# Boost_DC_DC.net
KiCad netlist of a schematic drawn in Altium Designer
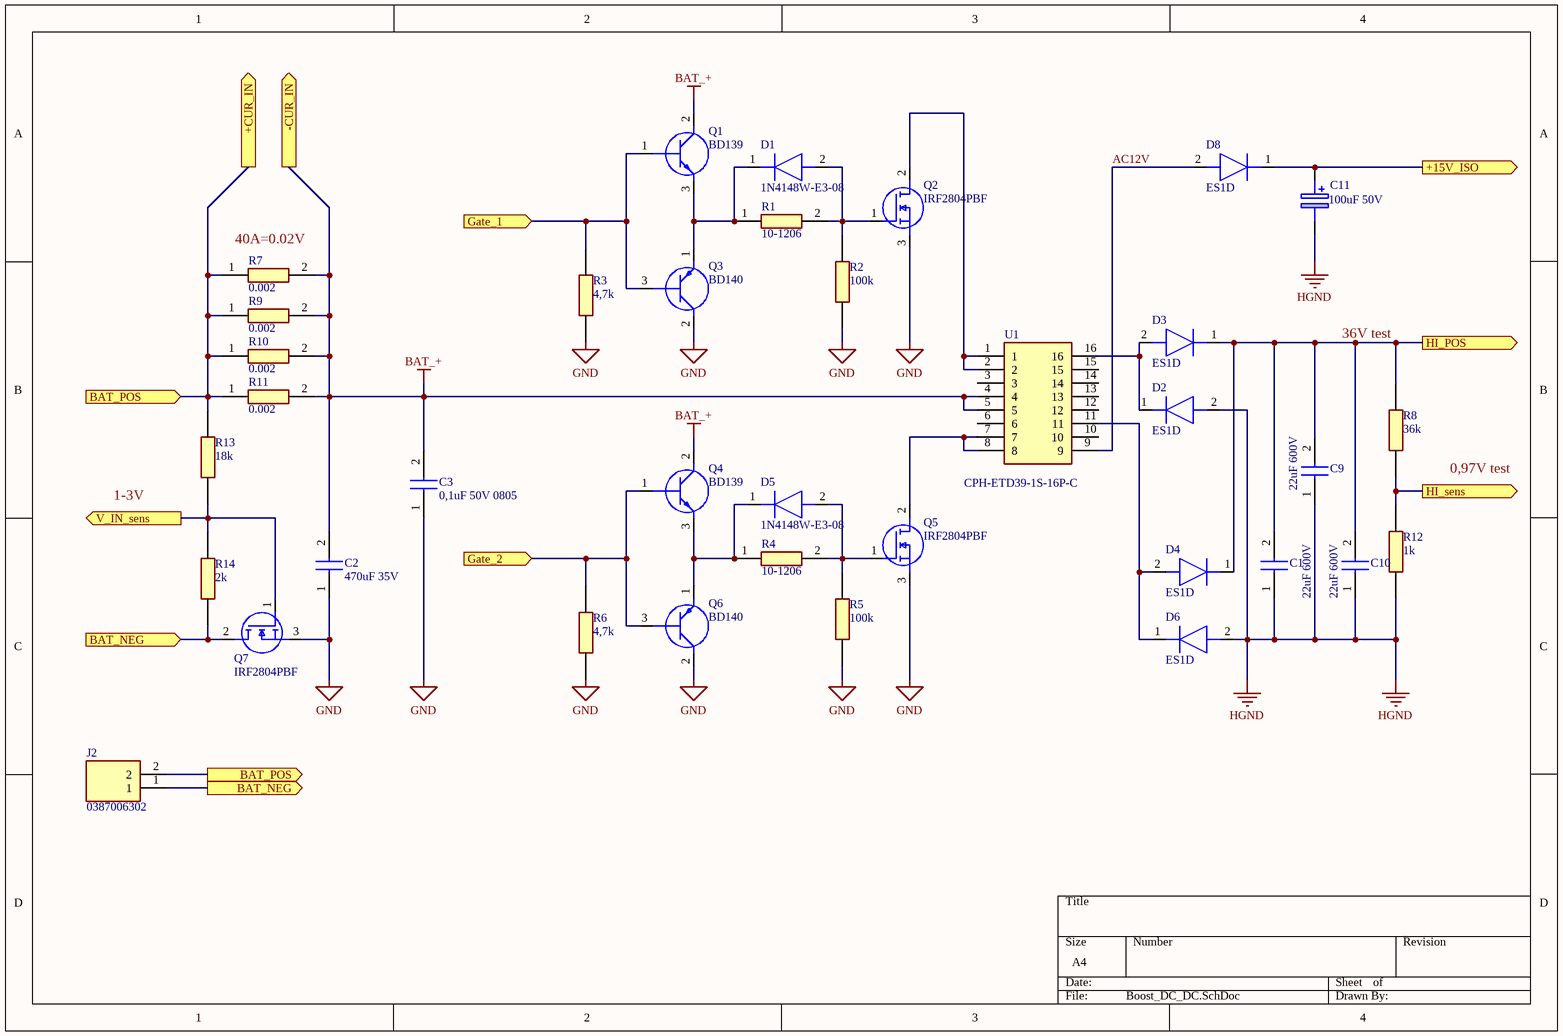
[diagram p0: Boost_DC_DC.SchDoc]

(export (version "E")
  (design (tool "Eeschema 10.0.6"))
  (components
    (comp (ref "C1")
      (value "22uF 600V")
      (footprint "SamacSys:CAPPRD750W80D1625H2700")
      (description "Capacitor")
      (libsource (lib "*") (part "UPW1H102MHD"))
    )
    (comp (ref "C2")
      (value "470uF 35V")
      (footprint "SamacSys:CAPPRD750W80D1625H2700")
      (description "Capacitor")
      (libsource (lib "*") (part "UPW1H102MHD"))
    )
    (comp (ref "C3")
      (value "0,1uF 50V 0805")
      (footprint "SamacSys:CAPC2012X90N")
      (description "Capacitor")
      (libsource (lib "*") (part "MCMT21N470F250CT"))
    )
    (comp (ref "C9")
      (value "22uF 600V")
      (footprint "SamacSys:CAPPRD750W80D1625H2700")
      (description "Capacitor")
      (libsource (lib "*") (part "UPW1H102MHD"))
    )
    (comp (ref "C10")
      (value "22uF 600V")
      (footprint "SamacSys:CAPPRD750W80D1625H2700")
      (description "Capacitor")
      (libsource (lib "*") (part "UPW1H102MHD"))
    )
    (comp (ref "C11")
      (value "100uF 50V")
      (footprint "CAPPRD500W60D870H1200")
      (description "Aluminum Electrolytic Capacitors - Radial Leaded 100uF 50V 20% Radial")
      (fields
        (field (name "MANUFACTURER_PART_NUMBER") "MAL203690109E3")
        (field (name "MOUSER PART NUMBER") "594-2222-036-90109")
      )
      (libsource (lib "MAL203690109E3") (part "MAL203690109E3"))
    )
    (comp (ref "D1")
      (value "1N4148W-E3-08")
      (footprint "SamacSys:SOD3716X135N")
      (description "Diode")
      (fields (field (name "MOUSER PART NUMBER") "78-1N4148W-E3-08"))
      (libsource (lib "*") (part "1N4148W-E3-08"))
    )
    (comp (ref "D2")
      (value "ES1D")
      (footprint "SamacSys:DIOM5226X295N")
      (description "Diode")
      (libsource (lib "SamacSys") (part "ES1D"))
    )
    (comp (ref "D3")
      (value "ES1D")
      (footprint "SamacSys:DIOM5226X295N")
      (description "Diode")
      (libsource (lib "SamacSys") (part "ES1D"))
    )
    (comp (ref "D4")
      (value "ES1D")
      (footprint "SamacSys:DIOM5226X295N")
      (description "Diode")
      (libsource (lib "SamacSys") (part "ES1D"))
    )
    (comp (ref "D5")
      (value "1N4148W-E3-08")
      (footprint "SamacSys:SOD3716X135N")
      (description "Diode")
      (fields (field (name "MOUSER PART NUMBER") "78-1N4148W-E3-08"))
      (libsource (lib "*") (part "1N4148W-E3-08"))
    )
    (comp (ref "D6")
      (value "ES1D")
      (footprint "SamacSys:DIOM5226X295N")
      (description "Diode")
      (libsource (lib "SamacSys") (part "ES1D"))
    )
    (comp (ref "D8")
      (value "ES1D")
      (footprint "SamacSys:DIOM5226X295N")
      (description "Diode")
      (libsource (lib "SamacSys") (part "ES1D"))
    )
    (comp (ref "J2")
      (value "0387006302")
      (footprint "SamacSys:0387006302")
      (description "Connector")
      (libsource (lib "*") (part "0387006302"))
    )
    (comp (ref "Q1")
      (value "BD139")
      (footprint "SamacSys:TO254P290X760X1320-3P")
      (description "Transistor BJT NPN")
      (fields (field (name "MOUSER PART NUMBER") "511-BD139"))
      (libsource (lib "*") (part "BD139"))
    )
    (comp (ref "Q2")
      (value "IRF2804PBF")
      (footprint "SamacSys:TO254P482X1016X2192-3P")
      (description "MOSFET (N-Channel)")
      (fields (field (name "MOUSER PART NUMBER") "942-IRF2804PBF"))
      (libsource (lib "*") (part "IRF2804PBF"))
    )
    (comp (ref "Q3")
      (value "BD140")
      (footprint "SamacSys:TO229P300X760X1364-3P")
      (description "Transistor BJT PNP")
      (fields
        (field (name "MANUFACTURER_PART_NUMBER") "BD138")
        (field (name "MOUSER PART NUMBER") "863-BD138")
      )
      (libsource (lib "*") (part "BD138"))
    )
    (comp (ref "Q4")
      (value "BD139")
      (footprint "SamacSys:TO254P290X760X1320-3P")
      (description "Transistor BJT NPN")
      (fields (field (name "MOUSER PART NUMBER") "511-BD139"))
      (libsource (lib "*") (part "BD139"))
    )
    (comp (ref "Q5")
      (value "IRF2804PBF")
      (footprint "SamacSys:TO254P482X1016X2192-3P")
      (description "MOSFET (N-Channel)")
      (fields (field (name "MOUSER PART NUMBER") "942-IRF2804PBF"))
      (libsource (lib "*") (part "IRF2804PBF"))
    )
    (comp (ref "Q6")
      (value "BD140")
      (footprint "SamacSys:TO229P300X760X1364-3P")
      (description "Transistor BJT PNP")
      (fields
        (field (name "MANUFACTURER_PART_NUMBER") "BD138")
        (field (name "MOUSER PART NUMBER") "863-BD138")
      )
      (libsource (lib "*") (part "BD138"))
    )
    (comp (ref "Q7")
      (value "IRF2804PBF")
      (footprint "SamacSys:TO254P482X1016X2192-3P")
      (description "MOSFET (N-Channel)")
      (fields (field (name "MOUSER PART NUMBER") "942-IRF2804PBF"))
      (libsource (lib "*") (part "IRF2804PBF"))
    )
    (comp (ref "R1")
      (value "10-1206")
      (footprint "SamacSys:RESC3116X75N")
      (description "Resistor")
      (libsource (lib "*") (part "MCMR12X1003FTL"))
    )
    (comp (ref "R2")
      (value "100k")
      (footprint "RESC2013X65N")
      (description "Resistor")
      (libsource (lib "SamacSys") (part "ERJP06J822V"))
    )
    (comp (ref "R3")
      (value "4,7k")
      (footprint "RESC2013X65N")
      (description "Resistor")
      (libsource (lib "SamacSys") (part "ERJP06J822V"))
    )
    (comp (ref "R4")
      (value "10-1206")
      (footprint "SamacSys:RESC3116X75N")
      (description "Resistor")
      (libsource (lib "*") (part "MCMR12X1003FTL"))
    )
    (comp (ref "R5")
      (value "100k")
      (footprint "RESC2013X65N")
      (description "Resistor")
      (libsource (lib "SamacSys") (part "ERJP06J822V"))
    )
    (comp (ref "R6")
      (value "4,7k")
      (footprint "RESC2013X65N")
      (description "Resistor")
      (libsource (lib "SamacSys") (part "ERJP06J822V"))
    )
    (comp (ref "R7")
      (value "0.002")
      (footprint "SamacSys:RESC3116X75N")
      (description "Resistor")
      (libsource (lib "*") (part "MCMR12X1003FTL"))
    )
    (comp (ref "R8")
      (value "36k")
      (footprint "RESC2013X65N")
      (description "Resistor")
      (libsource (lib "SamacSys") (part "ERJP06J822V"))
    )
    (comp (ref "R9")
      (value "0.002")
      (footprint "SamacSys:RESC3116X75N")
      (description "Resistor")
      (libsource (lib "*") (part "MCMR12X1003FTL"))
    )
    (comp (ref "R10")
      (value "0.002")
      (footprint "SamacSys:RESC3116X75N")
      (description "Resistor")
      (libsource (lib "*") (part "MCMR12X1003FTL"))
    )
    (comp (ref "R11")
      (value "0.002")
      (footprint "SamacSys:RESC3116X75N")
      (description "Resistor")
      (libsource (lib "*") (part "MCMR12X1003FTL"))
    )
    (comp (ref "R12")
      (value "1k")
      (footprint "RESC2013X65N")
      (description "Resistor")
      (libsource (lib "SamacSys") (part "ERJP06J822V"))
    )
    (comp (ref "R13")
      (value "18k")
      (footprint "RESC2013X65N")
      (description "Resistor")
      (libsource (lib "SamacSys") (part "ERJP06J822V"))
    )
    (comp (ref "R14")
      (value "2k")
      (footprint "RESC2013X65N")
      (description "Resistor")
      (libsource (lib "SamacSys") (part "ERJP06J822V"))
    )
    (comp (ref "U1")
      (value "CPH-ETD39-1S-16P-C")
      (footprint "SamacSys:DIPS3048W80P508L4460H3610Q16N")
      (description "Undefined or Miscellaneous")
      (libsource (lib "SamacSys") (part "CPH-ETD39-1S-16P-C"))
    )
  )
  (nets
    (net (code "1") (name "/+15V_ISO") (class "Default")
      (node (ref "C11") (pin "1") (pinfunction "+_1") (pintype "passive"))
      (node (ref "D8") (pin "1") (pinfunction "K_1") (pintype "passive"))
    )
    (net (code "2") (name "/+CUR_IN") (class "Default")
      (node (ref "J2") (pin "2") (pinfunction "2_2") (pintype "passive"))
      (node (ref "R10") (pin "1") (pinfunction "1_1") (pintype "passive"))
      (node (ref "R11") (pin "1") (pinfunction "1_1") (pintype "passive"))
      (node (ref "R13") (pin "2") (pinfunction "2_2") (pintype "passive"))
      (node (ref "R7") (pin "1") (pinfunction "1_1") (pintype "passive"))
      (node (ref "R9") (pin "1") (pinfunction "1_1") (pintype "passive"))
    )
    (net (code "3") (name "/AC12V") (class "Default")
      (node (ref "D8") (pin "2") (pinfunction "A_2") (pintype "passive"))
      (node (ref "U1") (pin "9") (pinfunction "9_9") (pintype "passive"))
    )
    (net (code "4") (name "/BAT_NEG") (class "Default")
      (node (ref "J2") (pin "1") (pinfunction "1_1") (pintype "passive"))
      (node (ref "Q7") (pin "2") (pinfunction "D_2") (pintype "passive"))
      (node (ref "R14") (pin "1") (pinfunction "1_1") (pintype "passive"))
    )
    (net (code "5") (name "/Gate_1") (class "Default")
      (node (ref "Q1") (pin "1") (pinfunction "B_1") (pintype "passive"))
      (node (ref "Q3") (pin "3") (pinfunction "B_3") (pintype "passive"))
      (node (ref "R3") (pin "2") (pinfunction "2_2") (pintype "passive"))
    )
    (net (code "6") (name "/Gate_2") (class "Default")
      (node (ref "Q4") (pin "1") (pinfunction "B_1") (pintype "passive"))
      (node (ref "Q6") (pin "3") (pinfunction "B_3") (pintype "passive"))
      (node (ref "R6") (pin "2") (pinfunction "2_2") (pintype "passive"))
    )
    (net (code "7") (name "/HI_POS") (class "Default")
      (node (ref "C1") (pin "2") (pinfunction "-_2") (pintype "passive"))
      (node (ref "C10") (pin "2") (pinfunction "-_2") (pintype "passive"))
      (node (ref "C9") (pin "2") (pinfunction "-_2") (pintype "passive"))
      (node (ref "D3") (pin "1") (pinfunction "K_1") (pintype "passive"))
      (node (ref "D4") (pin "1") (pinfunction "K_1") (pintype "passive"))
      (node (ref "R8") (pin "2") (pinfunction "2_2") (pintype "passive"))
    )
    (net (code "8") (name "/HI_sens") (class "Default")
      (node (ref "R12") (pin "2") (pinfunction "2_2") (pintype "passive"))
      (node (ref "R8") (pin "1") (pinfunction "1_1") (pintype "passive"))
    )
    (net (code "9") (name "/V_IN_sens") (class "Default")
      (node (ref "Q7") (pin "1") (pinfunction "G_1") (pintype "passive"))
      (node (ref "R13") (pin "1") (pinfunction "1_1") (pintype "passive"))
      (node (ref "R14") (pin "2") (pinfunction "2_2") (pintype "passive"))
    )
    (net (code "10") (name "BAT_+") (class "Default")
      (node (ref "C2") (pin "2") (pinfunction "-_2") (pintype "passive"))
      (node (ref "C3") (pin "2") (pinfunction "2_2") (pintype "passive"))
      (node (ref "Q1") (pin "2") (pinfunction "C_2") (pintype "passive"))
      (node (ref "Q4") (pin "2") (pinfunction "C_2") (pintype "passive"))
      (node (ref "R10") (pin "2") (pinfunction "2_2") (pintype "passive"))
      (node (ref "R11") (pin "2") (pinfunction "2_2") (pintype "passive"))
      (node (ref "R7") (pin "2") (pinfunction "2_2") (pintype "passive"))
      (node (ref "R9") (pin "2") (pinfunction "2_2") (pintype "passive"))
      (node (ref "U1") (pin "4") (pinfunction "4_4") (pintype "passive"))
      (node (ref "U1") (pin "5") (pinfunction "5_5") (pintype "passive"))
    )
    (net (code "11") (name "GND") (class "Default")
      (node (ref "C2") (pin "1") (pinfunction "+_1") (pintype "passive"))
      (node (ref "C3") (pin "1") (pinfunction "1_1") (pintype "passive"))
      (node (ref "Q2") (pin "3") (pinfunction "S_3") (pintype "passive"))
      (node (ref "Q3") (pin "2") (pinfunction "C_2") (pintype "passive"))
      (node (ref "Q5") (pin "3") (pinfunction "S_3") (pintype "passive"))
      (node (ref "Q6") (pin "2") (pinfunction "C_2") (pintype "passive"))
      (node (ref "Q7") (pin "3") (pinfunction "S_3") (pintype "passive"))
      (node (ref "R2") (pin "1") (pinfunction "1_1") (pintype "passive"))
      (node (ref "R3") (pin "1") (pinfunction "1_1") (pintype "passive"))
      (node (ref "R5") (pin "1") (pinfunction "1_1") (pintype "passive"))
      (node (ref "R6") (pin "1") (pinfunction "1_1") (pintype "passive"))
    )
    (net (code "12") (name "HGND") (class "Default")
      (node (ref "C1") (pin "1") (pinfunction "+_1") (pintype "passive"))
      (node (ref "C10") (pin "1") (pinfunction "+_1") (pintype "passive"))
      (node (ref "C11") (pin "2") (pinfunction "-_2") (pintype "passive"))
      (node (ref "C9") (pin "1") (pinfunction "+_1") (pintype "passive"))
      (node (ref "D2") (pin "2") (pinfunction "A_2") (pintype "passive"))
      (node (ref "D6") (pin "2") (pinfunction "A_2") (pintype "passive"))
      (node (ref "R12") (pin "1") (pinfunction "1_1") (pintype "passive"))
    )
    (net (code "13") (name "Net-(D1-A)") (class "Default")
      (node (ref "D1") (pin "2") (pinfunction "A_2") (pintype "passive"))
      (node (ref "Q2") (pin "1") (pinfunction "G_1") (pintype "passive"))
      (node (ref "R1") (pin "2") (pinfunction "2_2") (pintype "passive"))
      (node (ref "R2") (pin "2") (pinfunction "2_2") (pintype "passive"))
    )
    (net (code "14") (name "Net-(D1-K)") (class "Default")
      (node (ref "D1") (pin "1") (pinfunction "K_1") (pintype "passive"))
      (node (ref "Q1") (pin "3") (pinfunction "E_3") (pintype "passive"))
      (node (ref "Q3") (pin "1") (pinfunction "E_1") (pintype "passive"))
      (node (ref "R1") (pin "1") (pinfunction "1_1") (pintype "passive"))
    )
    (net (code "15") (name "Net-(D2-K)") (class "Default")
      (node (ref "D2") (pin "1") (pinfunction "K_1") (pintype "passive"))
      (node (ref "D3") (pin "2") (pinfunction "A_2") (pintype "passive"))
      (node (ref "U1") (pin "16") (pinfunction "16_16") (pintype "passive"))
    )
    (net (code "16") (name "Net-(D4-A)") (class "Default")
      (node (ref "D4") (pin "2") (pinfunction "A_2") (pintype "passive"))
      (node (ref "D6") (pin "1") (pinfunction "K_1") (pintype "passive"))
      (node (ref "U1") (pin "11") (pinfunction "11_11") (pintype "passive"))
    )
    (net (code "17") (name "Net-(D5-A)") (class "Default")
      (node (ref "D5") (pin "2") (pinfunction "A_2") (pintype "passive"))
      (node (ref "Q5") (pin "1") (pinfunction "G_1") (pintype "passive"))
      (node (ref "R4") (pin "2") (pinfunction "2_2") (pintype "passive"))
      (node (ref "R5") (pin "2") (pinfunction "2_2") (pintype "passive"))
    )
    (net (code "18") (name "Net-(D5-K)") (class "Default")
      (node (ref "D5") (pin "1") (pinfunction "K_1") (pintype "passive"))
      (node (ref "Q4") (pin "3") (pinfunction "E_3") (pintype "passive"))
      (node (ref "Q6") (pin "1") (pinfunction "E_1") (pintype "passive"))
      (node (ref "R4") (pin "1") (pinfunction "1_1") (pintype "passive"))
    )
    (net (code "19") (name "Net-(Q2-D)") (class "Default")
      (node (ref "Q2") (pin "2") (pinfunction "D_2") (pintype "passive"))
      (node (ref "U1") (pin "1") (pinfunction "1_1") (pintype "passive"))
      (node (ref "U1") (pin "2") (pinfunction "2_2") (pintype "passive"))
    )
    (net (code "20") (name "Net-(Q5-D)") (class "Default")
      (node (ref "Q5") (pin "2") (pinfunction "D_2") (pintype "passive"))
      (node (ref "U1") (pin "7") (pinfunction "7_7") (pintype "passive"))
      (node (ref "U1") (pin "8") (pinfunction "8_8") (pintype "passive"))
    )
    (net (code "21") (name "unconnected-(U1-Pad3)") (class "Default")
      (node (ref "U1") (pin "3") (pinfunction "3_3") (pintype "passive"))
    )
    (net (code "22") (name "unconnected-(U1-Pad6)") (class "Default")
      (node (ref "U1") (pin "6") (pinfunction "6_6") (pintype "passive"))
    )
    (net (code "23") (name "unconnected-(U1-Pad10)") (class "Default")
      (node (ref "U1") (pin "10") (pinfunction "10_10") (pintype "passive"))
    )
    (net (code "24") (name "unconnected-(U1-Pad12)") (class "Default")
      (node (ref "U1") (pin "12") (pinfunction "12_12") (pintype "passive"))
    )
    (net (code "25") (name "unconnected-(U1-Pad13)") (class "Default")
      (node (ref "U1") (pin "13") (pinfunction "13_13") (pintype "passive"))
    )
    (net (code "26") (name "unconnected-(U1-Pad14)") (class "Default")
      (node (ref "U1") (pin "14") (pinfunction "14_14") (pintype "passive"))
    )
    (net (code "27") (name "unconnected-(U1-Pad15)") (class "Default")
      (node (ref "U1") (pin "15") (pinfunction "15_15") (pintype "passive"))
    )
  )
)
